# emonPlug_v1-1.net
KiCad netlist of a schematic drawn in EAGLE
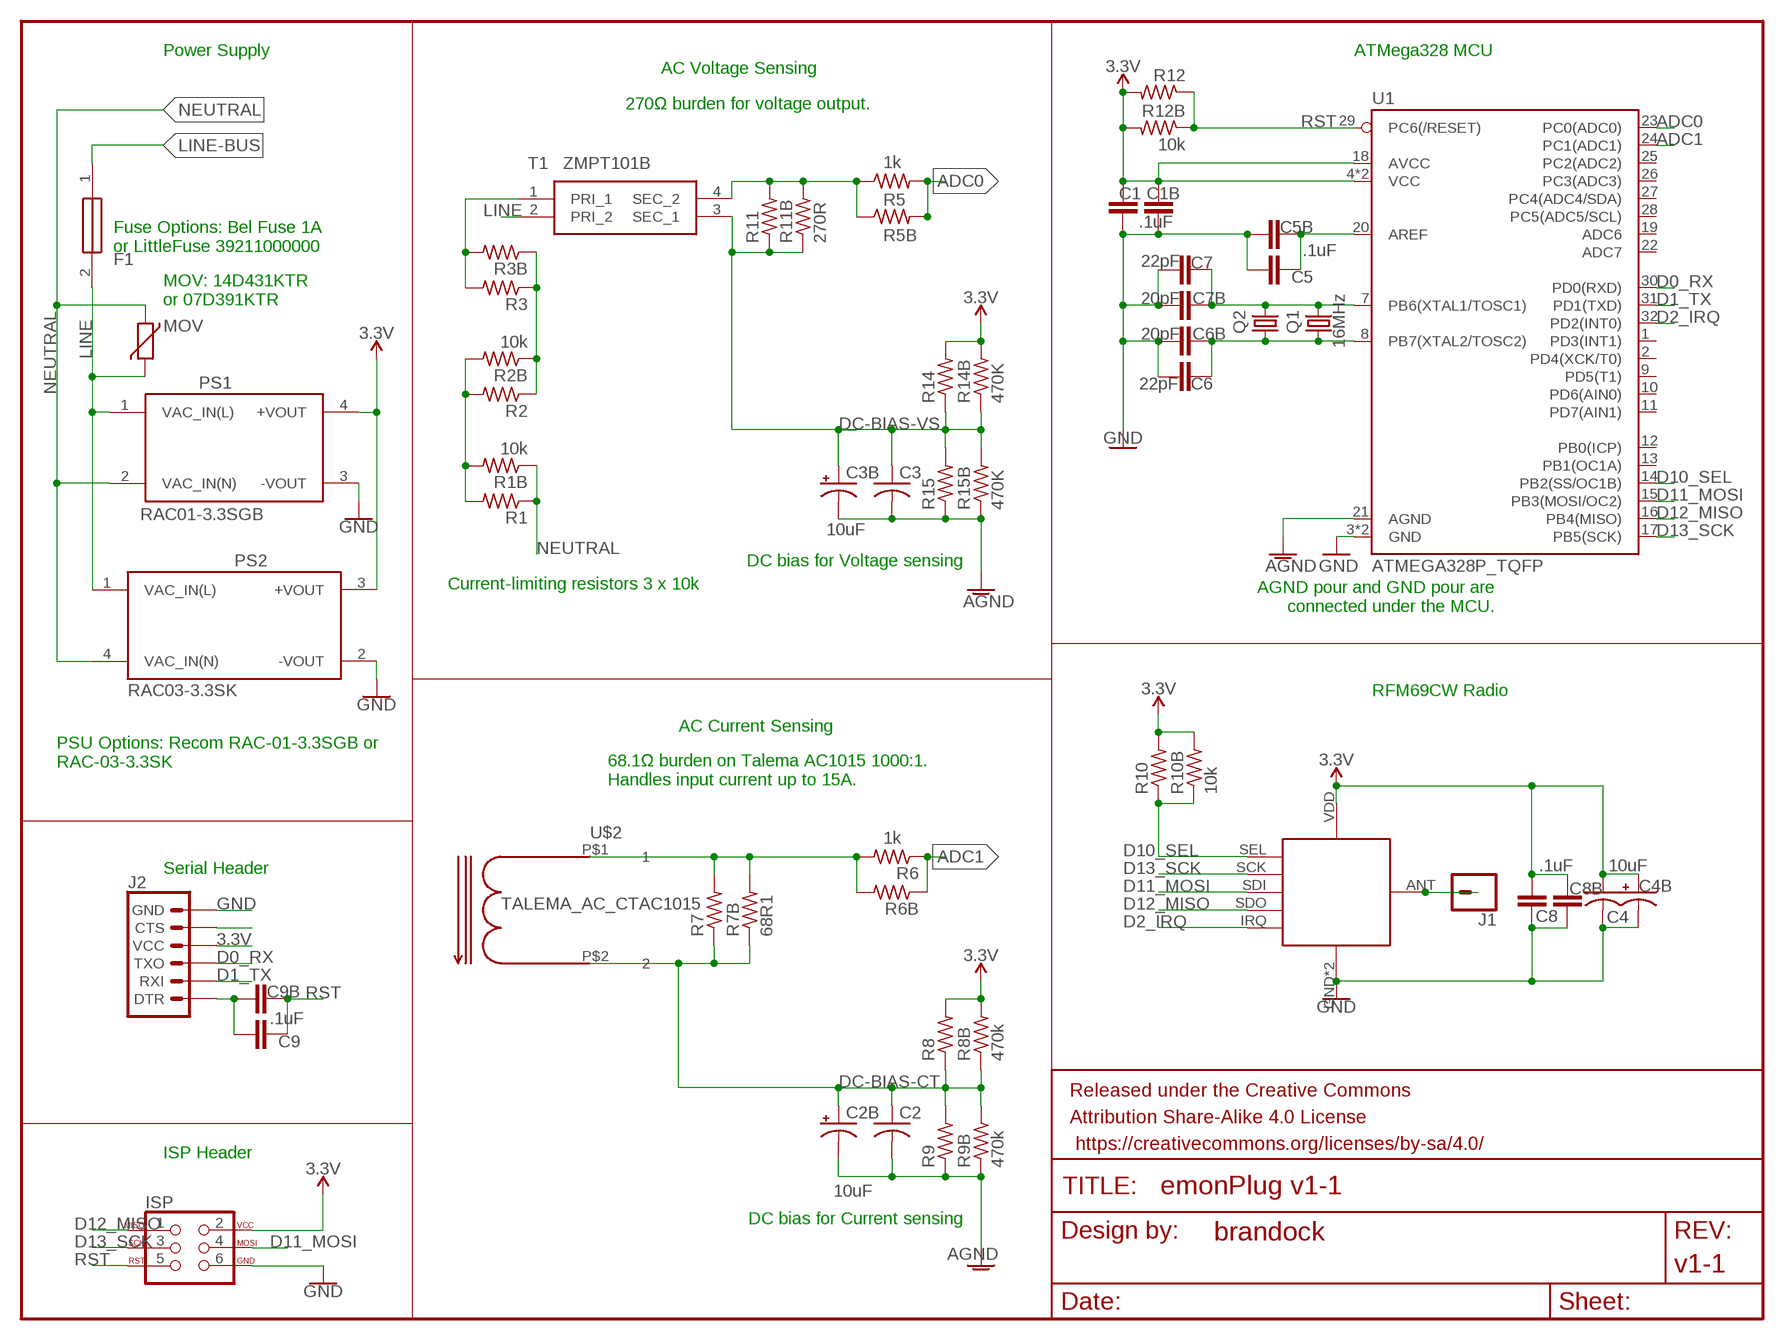
[diagram p0: schematic, sheet 1]

(export (version "E")
  (design (tool "Eeschema 10.0.6"))
  (components
    (comp (ref "C1")
      (value ".1uF")
      (footprint "eagle-import:C0805")
      (libsource (lib "eagle-import") (part "C-EUC0805"))
    )
    (comp (ref "C1B")
      (value ".1uF")
      (footprint "eagle-import:C025-024X044")
      (libsource (lib "eagle-import") (part "rcl_334_C-EU025-024X044"))
    )
    (comp (ref "C2")
      (value "C-USC0805")
      (footprint "eagle-import:C0805")
      (libsource (lib "eagle-import") (part "C-USC0805"))
    )
    (comp (ref "C2B")
      (value "10uF")
      (footprint "eagle-import:E1,8-4")
      (libsource (lib "eagle-import") (part "CPOL-USE1.8-4"))
    )
    (comp (ref "C3")
      (value "C-USC0805")
      (footprint "eagle-import:C0805")
      (libsource (lib "eagle-import") (part "C-USC0805"))
    )
    (comp (ref "C3B")
      (value "10uF")
      (footprint "eagle-import:E1,8-4")
      (libsource (lib "eagle-import") (part "CPOL-USE1.8-4"))
    )
    (comp (ref "C4")
      (value "10uF")
      (footprint "eagle-import:C0805")
      (libsource (lib "eagle-import") (part "C-USC0805"))
    )
    (comp (ref "C4B")
      (value "10uF")
      (footprint "eagle-import:E1,8-4")
      (libsource (lib "eagle-import") (part "CPOL-USE1.8-4"))
    )
    (comp (ref "C5")
      (value ".1uF")
      (footprint "eagle-import:C0805")
      (libsource (lib "eagle-import") (part "C-EUC0805"))
    )
    (comp (ref "C5B")
      (value ".1uF")
      (footprint "eagle-import:C025-024X044")
      (libsource (lib "eagle-import") (part "rcl_334_C-EU025-024X044"))
    )
    (comp (ref "C6")
      (value "22pF")
      (footprint "eagle-import:C0805")
      (libsource (lib "eagle-import") (part "C-EUC0805"))
    )
    (comp (ref "C6B")
      (value "20pF")
      (footprint "eagle-import:C025-024X044")
      (libsource (lib "eagle-import") (part "rcl_334_C-EU025-024X044"))
    )
    (comp (ref "C7")
      (value "22pF")
      (footprint "eagle-import:C0805")
      (libsource (lib "eagle-import") (part "C-EUC0805"))
    )
    (comp (ref "C7B")
      (value "20pF")
      (footprint "eagle-import:C025-024X044")
      (libsource (lib "eagle-import") (part "rcl_334_C-EU025-024X044"))
    )
    (comp (ref "C8")
      (value ".1uF")
      (footprint "eagle-import:C0805")
      (libsource (lib "eagle-import") (part "C-EUC0805"))
    )
    (comp (ref "C8B")
      (value ".1uF")
      (footprint "eagle-import:C025-024X044")
      (libsource (lib "eagle-import") (part "rcl_334_C-EU025-024X044"))
    )
    (comp (ref "C9")
      (value ".1uF")
      (footprint "eagle-import:C0805")
      (libsource (lib "eagle-import") (part "C-EUC0805"))
    )
    (comp (ref "C9B")
      (value ".1uF")
      (footprint "eagle-import:C025-024X044")
      (libsource (lib "eagle-import") (part "rcl_334_C-EU025-024X044"))
    )
    (comp (ref "F1")
      (value "39211000000")
      (footprint "eagle-import:39211000000")
      (fields (field (name "MOUSER_PART_NUMBER") "576-3921100000"))
      (libsource (lib "eagle-import") (part "39211000000"))
    )
    (comp (ref "FRAME1")
      (value "FRAME-LETTER")
      (footprint "eagle-import:CREATIVE_COMMONS")
      (fields (field (name "DESIGNER") "brandock") (field (name "REV") "v1-1"))
      (libsource (lib "eagle-import") (part "FRAME-LETTER"))
    )
    (comp (ref "ISP")
      (value "AVR_SPI_PROG_3X22X3_LOCK")
      (footprint "eagle-import:2X3_LOCK")
      (libsource (lib "eagle-import") (part "AVR_SPI_PROG_3X22X3_LOCK"))
    )
    (comp (ref "J1")
      (value "CONN_01")
      (footprint "eagle-import:1X01")
      (libsource (lib "eagle-import") (part "CONN_01"))
    )
    (comp (ref "J2")
      (value "6_PIN_SERIAL_TARGET_SILK")
      (footprint "eagle-import:1X06")
      (libsource (lib "eagle-import") (part "6_PIN_SERIAL_TARGET_SILK"))
    )
    (comp (ref "MOV")
      (value "VARISTOR-5")
      (footprint "eagle-import:R-5")
      (libsource (lib "eagle-import") (part "VARISTOR-5"))
    )
    (comp (ref "PS1")
      (value "RAC01-3.3SGB")
      (footprint "eagle-import:CONV_RAC01-3.3SGB")
      (fields (field (name "MF") "Recom Power"))
      (libsource (lib "eagle-import") (part "RAC01-3.3SGB"))
    )
    (comp (ref "PS2")
      (value "RAC03-3.3SK")
      (footprint "eagle-import:CONV_RAC03-3.3SK")
      (fields (field (name "MF") "Recom Power"))
      (libsource (lib "eagle-import") (part "RAC03-3.3SK"))
    )
    (comp (ref "Q1")
      (value "16MHz")
      (footprint "eagle-import:HC49_S-NO-SILK")
      (libsource (lib "eagle-import") (part "CRYSTALHC49S-NOSILK"))
    )
    (comp (ref "Q2")
      (value "CRYSTALHC49UP")
      (footprint "eagle-import:HC49UP")
      (libsource (lib "eagle-import") (part "crystal_204_CRYSTALHC49UP"))
    )
    (comp (ref "R1")
      (value "R-US_R0805")
      (footprint "eagle-import:R0805")
      (libsource (lib "eagle-import") (part "rcl_334_R-US_R0805"))
    )
    (comp (ref "R1B")
      (value "10k")
      (footprint "eagle-import:0204_7")
      (libsource (lib "eagle-import") (part "R-US_0204/7"))
    )
    (comp (ref "R2")
      (value "R-US_R0805")
      (footprint "eagle-import:R0805")
      (libsource (lib "eagle-import") (part "rcl_334_R-US_R0805"))
    )
    (comp (ref "R2B")
      (value "10k")
      (footprint "eagle-import:0204_7")
      (libsource (lib "eagle-import") (part "R-US_0204/7"))
    )
    (comp (ref "R3")
      (value "R-US_R0805")
      (footprint "eagle-import:R0805")
      (libsource (lib "eagle-import") (part "rcl_334_R-US_R0805"))
    )
    (comp (ref "R3B")
      (value "R-US_0204/7")
      (footprint "eagle-import:0204_7")
      (libsource (lib "eagle-import") (part "R-US_0204/7"))
    )
    (comp (ref "R5")
      (value "1k")
      (footprint "eagle-import:R0805")
      (libsource (lib "eagle-import") (part "rcl_334_R-US_R0805"))
    )
    (comp (ref "R5B")
      (value "R-US_0204/7")
      (footprint "eagle-import:0204_7")
      (libsource (lib "eagle-import") (part "R-US_0204/7"))
    )
    (comp (ref "R6")
      (value "R-US_R0805")
      (footprint "eagle-import:R0805")
      (libsource (lib "eagle-import") (part "rcl_334_R-US_R0805"))
    )
    (comp (ref "R6B")
      (value "1k")
      (footprint "eagle-import:0204_7")
      (libsource (lib "eagle-import") (part "R-US_0204/7"))
    )
    (comp (ref "R7")
      (value "R-US_R0805")
      (footprint "eagle-import:R0805")
      (libsource (lib "eagle-import") (part "rcl_334_R-US_R0805"))
    )
    (comp (ref "R7B")
      (value "68R1")
      (footprint "eagle-import:0204_7")
      (libsource (lib "eagle-import") (part "R-US_0204/7"))
    )
    (comp (ref "R8")
      (value "R-US_R0805")
      (footprint "eagle-import:R0805")
      (libsource (lib "eagle-import") (part "rcl_334_R-US_R0805"))
    )
    (comp (ref "R8B")
      (value "470k")
      (footprint "eagle-import:0204_7")
      (libsource (lib "eagle-import") (part "R-US_0204/7"))
    )
    (comp (ref "R9")
      (value "R-US_R0805")
      (footprint "eagle-import:R0805")
      (libsource (lib "eagle-import") (part "rcl_334_R-US_R0805"))
    )
    (comp (ref "R9B")
      (value "470k")
      (footprint "eagle-import:0204_7")
      (libsource (lib "eagle-import") (part "R-US_0204/7"))
    )
    (comp (ref "R10")
      (value "R-US_R0805")
      (footprint "eagle-import:R0805")
      (libsource (lib "eagle-import") (part "rcl_334_R-US_R0805"))
    )
    (comp (ref "R10B")
      (value "10k")
      (footprint "eagle-import:0204_7")
      (libsource (lib "eagle-import") (part "R-US_0204/7"))
    )
    (comp (ref "R11")
      (value "R-US_R0805")
      (footprint "eagle-import:R0805")
      (libsource (lib "eagle-import") (part "rcl_334_R-US_R0805"))
    )
    (comp (ref "R11B")
      (value "270R")
      (footprint "eagle-import:0204_7")
      (libsource (lib "eagle-import") (part "R-US_0204/7"))
    )
    (comp (ref "R12")
      (value "R-US_R0805")
      (footprint "eagle-import:R0805")
      (libsource (lib "eagle-import") (part "rcl_334_R-US_R0805"))
    )
    (comp (ref "R12B")
      (value "10k")
      (footprint "eagle-import:0204_7")
      (libsource (lib "eagle-import") (part "R-US_0204/7"))
    )
    (comp (ref "R14")
      (value "R-US_R0805")
      (footprint "eagle-import:R0805")
      (libsource (lib "eagle-import") (part "rcl_334_R-US_R0805"))
    )
    (comp (ref "R14B")
      (value "470K")
      (footprint "eagle-import:0204_7")
      (libsource (lib "eagle-import") (part "R-US_0204/7"))
    )
    (comp (ref "R15")
      (value "R-US_R0805")
      (footprint "eagle-import:R0805")
      (libsource (lib "eagle-import") (part "rcl_334_R-US_R0805"))
    )
    (comp (ref "R15B")
      (value "470K")
      (footprint "eagle-import:0204_7")
      (libsource (lib "eagle-import") (part "R-US_0204/7"))
    )
    (comp (ref "T1")
      (value "ZMPT101B")
      (footprint "eagle-import:ZMPT101B")
      (libsource (lib "eagle-import") (part "ZMPT101B"))
    )
    (comp (ref "U$2")
      (value "TALEMA_AC_CTAC1015")
      (footprint "eagle-import:AC1005-1020")
      (libsource (lib "eagle-import") (part "TALEMA_AC_CTAC1015"))
    )
    (comp (ref "U$3")
      (value "RFM12B_MINPADS")
      (footprint "eagle-import:RFM12B-MINPADS")
      (libsource (lib "eagle-import") (part "RFM12B_MINPADS"))
    )
    (comp (ref "U1")
      (value "ATMEGA328P_TQFP")
      (footprint "eagle-import:TQFP32-08")
      (libsource (lib "eagle-import") (part "ATMEGA328P_TQFP"))
    )
  )
  (nets
    (net (code "1") (name "3.3V") (class "Default")
      (node (ref "C1") (pin "2") (pinfunction "2_2") (pintype "passive"))
      (node (ref "C1B") (pin "1") (pinfunction "1_1") (pintype "passive"))
      (node (ref "C4") (pin "1") (pinfunction "1_1") (pintype "passive"))
      (node (ref "C4B") (pin "+") (pinfunction "+_+") (pintype "passive"))
      (node (ref "C8") (pin "1") (pinfunction "1_1") (pintype "passive"))
      (node (ref "C8B") (pin "1") (pinfunction "1_1") (pintype "passive"))
      (node (ref "ISP") (pin "2") (pinfunction "2_2") (pintype "passive"))
      (node (ref "J2") (pin "4") (pinfunction "VCC_4") (pintype "passive"))
      (node (ref "PS1") (pin "4") (pinfunction "+VOUT_4") (pintype "output"))
      (node (ref "PS2") (pin "3") (pinfunction "+VOUT_3") (pintype "output"))
      (node (ref "R10") (pin "2") (pinfunction "2_2") (pintype "passive"))
      (node (ref "R10B") (pin "2") (pinfunction "2_2") (pintype "passive"))
      (node (ref "R12") (pin "2") (pinfunction "2_2") (pintype "passive"))
      (node (ref "R12B") (pin "2") (pinfunction "2_2") (pintype "passive"))
      (node (ref "R14") (pin "2") (pinfunction "2_2") (pintype "passive"))
      (node (ref "R14B") (pin "2") (pinfunction "2_2") (pintype "passive"))
      (node (ref "R8") (pin "2") (pinfunction "2_2") (pintype "passive"))
      (node (ref "R8B") (pin "2") (pinfunction "2_2") (pintype "passive"))
      (node (ref "U$3") (pin "VDD") (pinfunction "VDD_VDD") (pintype "bidirectional"))
      (node (ref "U1") (pin "18") (pinfunction "AVCC_18") (pintype "bidirectional"))
      (node (ref "U1") (pin "4") (pinfunction "VCC_4") (pintype "bidirectional"))
      (node (ref "U1") (pin "6") (pinfunction "VCC_6") (pintype "bidirectional"))
    )
    (net (code "2") (name "ADC0") (class "Default")
      (node (ref "R5") (pin "2") (pinfunction "2_2") (pintype "passive"))
      (node (ref "R5B") (pin "2") (pinfunction "2_2") (pintype "passive"))
      (node (ref "U1") (pin "23") (pinfunction "PC0(ADC0)_23") (pintype "bidirectional"))
    )
    (net (code "3") (name "ADC1") (class "Default")
      (node (ref "R6") (pin "1") (pinfunction "1_1") (pintype "passive"))
      (node (ref "R6B") (pin "1") (pinfunction "1_1") (pintype "passive"))
      (node (ref "U1") (pin "24") (pinfunction "PC1(ADC1)_24") (pintype "bidirectional"))
    )
    (net (code "4") (name "AGND") (class "Default")
      (node (ref "C2") (pin "2") (pinfunction "2_2") (pintype "passive"))
      (node (ref "C2B") (pin "-") (pinfunction "-_-") (pintype "passive"))
      (node (ref "C3") (pin "2") (pinfunction "2_2") (pintype "passive"))
      (node (ref "C3B") (pin "-") (pinfunction "-_-") (pintype "passive"))
      (node (ref "R15") (pin "1") (pinfunction "1_1") (pintype "passive"))
      (node (ref "R15B") (pin "1") (pinfunction "1_1") (pintype "passive"))
      (node (ref "R9") (pin "1") (pinfunction "1_1") (pintype "passive"))
      (node (ref "R9B") (pin "1") (pinfunction "1_1") (pintype "passive"))
      (node (ref "U1") (pin "21") (pinfunction "AGND_21") (pintype "bidirectional"))
    )
    (net (code "5") (name "D0_RX") (class "Default")
      (node (ref "J2") (pin "3") (pinfunction "TXO_3") (pintype "passive"))
      (node (ref "U1") (pin "30") (pinfunction "PD0(RXD)_30") (pintype "bidirectional"))
    )
    (net (code "6") (name "D1_TX") (class "Default")
      (node (ref "J2") (pin "2") (pinfunction "RXI_2") (pintype "passive"))
      (node (ref "U1") (pin "31") (pinfunction "PD1(TXD)_31") (pintype "bidirectional"))
    )
    (net (code "7") (name "D2_IRQ") (class "Default")
      (node (ref "U$3") (pin "IRQ") (pinfunction "IRQ_IRQ") (pintype "bidirectional"))
      (node (ref "U1") (pin "32") (pinfunction "PD2(INT0)_32") (pintype "bidirectional"))
    )
    (net (code "8") (name "D10_SEL") (class "Default")
      (node (ref "R10") (pin "1") (pinfunction "1_1") (pintype "passive"))
      (node (ref "R10B") (pin "1") (pinfunction "1_1") (pintype "passive"))
      (node (ref "U$3") (pin "SEL") (pinfunction "SEL_SEL") (pintype "bidirectional"))
      (node (ref "U1") (pin "14") (pinfunction "PB2(SS/OC1B)_14") (pintype "bidirectional"))
    )
    (net (code "9") (name "D11_MOSI") (class "Default")
      (node (ref "ISP") (pin "4") (pinfunction "4_4") (pintype "passive"))
      (node (ref "U$3") (pin "SDI") (pinfunction "SDI/MOSI_SDI") (pintype "bidirectional"))
      (node (ref "U1") (pin "15") (pinfunction "PB3(MOSI/OC2)_15") (pintype "bidirectional"))
    )
    (net (code "10") (name "D12_MISO") (class "Default")
      (node (ref "ISP") (pin "1") (pinfunction "1_1") (pintype "passive"))
      (node (ref "U$3") (pin "SDO") (pinfunction "SDO/MISO_SDO") (pintype "bidirectional"))
      (node (ref "U1") (pin "16") (pinfunction "PB4(MISO)_16") (pintype "bidirectional"))
    )
    (net (code "11") (name "D13_SCK") (class "Default")
      (node (ref "ISP") (pin "3") (pinfunction "3_3") (pintype "passive"))
      (node (ref "U$3") (pin "SCK") (pinfunction "SCK_SCK") (pintype "bidirectional"))
      (node (ref "U1") (pin "17") (pinfunction "PB5(SCK)_17") (pintype "bidirectional"))
    )
    (net (code "12") (name "DC-BIAS-CT") (class "Default")
      (node (ref "C2") (pin "1") (pinfunction "1_1") (pintype "passive"))
      (node (ref "C2B") (pin "+") (pinfunction "+_+") (pintype "passive"))
      (node (ref "R7") (pin "1") (pinfunction "1_1") (pintype "passive"))
      (node (ref "R7B") (pin "1") (pinfunction "1_1") (pintype "passive"))
      (node (ref "R8") (pin "1") (pinfunction "1_1") (pintype "passive"))
      (node (ref "R8B") (pin "1") (pinfunction "1_1") (pintype "passive"))
      (node (ref "R9") (pin "2") (pinfunction "2_2") (pintype "passive"))
      (node (ref "R9B") (pin "2") (pinfunction "2_2") (pintype "passive"))
      (node (ref "U$2") (pin "P$2") (pinfunction "2_P$2") (pintype "bidirectional"))
    )
    (net (code "13") (name "DC-BIAS-VS") (class "Default")
      (node (ref "C3") (pin "1") (pinfunction "1_1") (pintype "passive"))
      (node (ref "C3B") (pin "+") (pinfunction "+_+") (pintype "passive"))
      (node (ref "R11") (pin "1") (pinfunction "1_1") (pintype "passive"))
      (node (ref "R11B") (pin "1") (pinfunction "1_1") (pintype "passive"))
      (node (ref "R14") (pin "1") (pinfunction "1_1") (pintype "passive"))
      (node (ref "R14B") (pin "1") (pinfunction "1_1") (pintype "passive"))
      (node (ref "R15") (pin "2") (pinfunction "2_2") (pintype "passive"))
      (node (ref "R15B") (pin "2") (pinfunction "2_2") (pintype "passive"))
      (node (ref "T1") (pin "3") (pinfunction "SEC_1_3") (pintype "bidirectional"))
    )
    (net (code "14") (name "GND") (class "Default")
      (node (ref "C1") (pin "1") (pinfunction "1_1") (pintype "passive"))
      (node (ref "C1B") (pin "2") (pinfunction "2_2") (pintype "passive"))
      (node (ref "C4") (pin "2") (pinfunction "2_2") (pintype "passive"))
      (node (ref "C4B") (pin "-") (pinfunction "-_-") (pintype "passive"))
      (node (ref "C5") (pin "1") (pinfunction "1_1") (pintype "passive"))
      (node (ref "C5B") (pin "1") (pinfunction "1_1") (pintype "passive"))
      (node (ref "C6") (pin "2") (pinfunction "2_2") (pintype "passive"))
      (node (ref "C6B") (pin "2") (pinfunction "2_2") (pintype "passive"))
      (node (ref "C7") (pin "2") (pinfunction "2_2") (pintype "passive"))
      (node (ref "C7B") (pin "2") (pinfunction "2_2") (pintype "passive"))
      (node (ref "C8") (pin "2") (pinfunction "2_2") (pintype "passive"))
      (node (ref "C8B") (pin "2") (pinfunction "2_2") (pintype "passive"))
      (node (ref "ISP") (pin "6") (pinfunction "6_6") (pintype "passive"))
      (node (ref "J2") (pin "6") (pinfunction "GND_6") (pintype "passive"))
      (node (ref "PS1") (pin "3") (pinfunction "-VOUT_3") (pintype "output"))
      (node (ref "PS2") (pin "2") (pinfunction "-VOUT_2") (pintype "output"))
      (node (ref "U$3") (pin "GND") (pinfunction "GND_GND") (pintype "bidirectional"))
      (node (ref "U$3") (pin "GND2") (pinfunction "GND_GND2") (pintype "bidirectional"))
      (node (ref "U1") (pin "3") (pinfunction "GND_3") (pintype "bidirectional"))
      (node (ref "U1") (pin "5") (pinfunction "GND_5") (pintype "bidirectional"))
    )
    (net (code "15") (name "LINE") (class "Default")
      (node (ref "F1") (pin "2") (pinfunction "2_2") (pintype "bidirectional"))
      (node (ref "MOV") (pin "1") (pinfunction "1_1") (pintype "passive"))
      (node (ref "PS1") (pin "1") (pinfunction "VAC_IN(L)_1") (pintype "input"))
      (node (ref "PS2") (pin "1") (pinfunction "VAC_IN(L)_1") (pintype "input"))
      (node (ref "T1") (pin "2") (pinfunction "PRI_2_2") (pintype "bidirectional"))
    )
    (net (code "16") (name "LINE-BUS") (class "Default")
      (node (ref "F1") (pin "1") (pinfunction "1_1") (pintype "bidirectional"))
    )
    (net (code "17") (name "NEUTRAL") (class "Default")
      (node (ref "MOV") (pin "2") (pinfunction "2_2") (pintype "passive"))
      (node (ref "PS1") (pin "2") (pinfunction "VAC_IN(N)_2") (pintype "input"))
      (node (ref "PS2") (pin "4") (pinfunction "VAC_IN(N)_4") (pintype "input"))
      (node (ref "R1") (pin "1") (pinfunction "1_1") (pintype "passive"))
      (node (ref "R1B") (pin "1") (pinfunction "1_1") (pintype "passive"))
    )
    (net (code "18") (name "Net-(J1-Pad1)") (class "Default")
      (node (ref "J1") (pin "1") (pinfunction "1_1") (pintype "passive"))
      (node (ref "U$3") (pin "ANT") (pinfunction "ANT_ANT") (pintype "bidirectional"))
    )
    (net (code "19") (name "Net-(J2-DTR)") (class "Default")
      (node (ref "C9") (pin "1") (pinfunction "1_1") (pintype "passive"))
      (node (ref "C9B") (pin "1") (pinfunction "1_1") (pintype "passive"))
      (node (ref "J2") (pin "1") (pinfunction "DTR_1") (pintype "passive"))
    )
    (net (code "20") (name "Net-(R1-Pad2)") (class "Default")
      (node (ref "R1") (pin "2") (pinfunction "2_2") (pintype "passive"))
      (node (ref "R1B") (pin "2") (pinfunction "2_2") (pintype "passive"))
      (node (ref "R2") (pin "2") (pinfunction "2_2") (pintype "passive"))
      (node (ref "R2B") (pin "2") (pinfunction "2_2") (pintype "passive"))
    )
    (net (code "21") (name "Net-(R2-Pad1)") (class "Default")
      (node (ref "R2") (pin "1") (pinfunction "1_1") (pintype "passive"))
      (node (ref "R2B") (pin "1") (pinfunction "1_1") (pintype "passive"))
      (node (ref "R3") (pin "1") (pinfunction "1_1") (pintype "passive"))
      (node (ref "R3B") (pin "1") (pinfunction "1_1") (pintype "passive"))
    )
    (net (code "22") (name "Net-(T1-PRI_1)") (class "Default")
      (node (ref "R3") (pin "2") (pinfunction "2_2") (pintype "passive"))
      (node (ref "R3B") (pin "2") (pinfunction "2_2") (pintype "passive"))
      (node (ref "T1") (pin "1") (pinfunction "PRI_1_1") (pintype "bidirectional"))
    )
    (net (code "23") (name "Net-(T1-SEC_2)") (class "Default")
      (node (ref "R11") (pin "2") (pinfunction "2_2") (pintype "passive"))
      (node (ref "R11B") (pin "2") (pinfunction "2_2") (pintype "passive"))
      (node (ref "R5") (pin "1") (pinfunction "1_1") (pintype "passive"))
      (node (ref "R5B") (pin "1") (pinfunction "1_1") (pintype "passive"))
      (node (ref "T1") (pin "4") (pinfunction "SEC_2_4") (pintype "bidirectional"))
    )
    (net (code "24") (name "Net-(U$2-1)") (class "Default")
      (node (ref "R6") (pin "2") (pinfunction "2_2") (pintype "passive"))
      (node (ref "R6B") (pin "2") (pinfunction "2_2") (pintype "passive"))
      (node (ref "R7") (pin "2") (pinfunction "2_2") (pintype "passive"))
      (node (ref "R7B") (pin "2") (pinfunction "2_2") (pintype "passive"))
      (node (ref "U$2") (pin "P$1") (pinfunction "1_P$1") (pintype "bidirectional"))
    )
    (net (code "25") (name "Net-(U1-AREF)") (class "Default")
      (node (ref "C5") (pin "2") (pinfunction "2_2") (pintype "passive"))
      (node (ref "C5B") (pin "2") (pinfunction "2_2") (pintype "passive"))
      (node (ref "U1") (pin "20") (pinfunction "AREF_20") (pintype "bidirectional"))
    )
    (net (code "26") (name "Net-(U1-PB6(XTAL1{slash}TOSC1))") (class "Default")
      (node (ref "C7") (pin "1") (pinfunction "1_1") (pintype "passive"))
      (node (ref "C7B") (pin "1") (pinfunction "1_1") (pintype "passive"))
      (node (ref "Q1") (pin "2") (pinfunction "2_2") (pintype "passive"))
      (node (ref "Q2") (pin "2") (pinfunction "2_2") (pintype "passive"))
      (node (ref "U1") (pin "7") (pinfunction "PB6(XTAL1/TOSC1)_7") (pintype "bidirectional"))
    )
    (net (code "27") (name "Net-(U1-PB7(XTAL2{slash}TOSC2))") (class "Default")
      (node (ref "C6") (pin "1") (pinfunction "1_1") (pintype "passive"))
      (node (ref "C6B") (pin "1") (pinfunction "1_1") (pintype "passive"))
      (node (ref "Q1") (pin "1") (pinfunction "1_1") (pintype "passive"))
      (node (ref "Q2") (pin "1") (pinfunction "1_1") (pintype "passive"))
      (node (ref "U1") (pin "8") (pinfunction "PB7(XTAL2/TOSC2)_8") (pintype "bidirectional"))
    )
    (net (code "28") (name "RST") (class "Default")
      (node (ref "C9") (pin "2") (pinfunction "2_2") (pintype "passive"))
      (node (ref "C9B") (pin "2") (pinfunction "2_2") (pintype "passive"))
      (node (ref "ISP") (pin "5") (pinfunction "5_5") (pintype "passive"))
      (node (ref "R12") (pin "1") (pinfunction "1_1") (pintype "passive"))
      (node (ref "R12B") (pin "1") (pinfunction "1_1") (pintype "passive"))
      (node (ref "U1") (pin "29") (pinfunction "PC6(/RESET)_29") (pintype "bidirectional"))
    )
    (net (code "29") (name "unconnected-(J2-CTS-Pad5)") (class "Default")
      (node (ref "J2") (pin "5") (pinfunction "CTS_5") (pintype "passive"))
    )
    (net (code "30") (name "unconnected-(U1-ADC6-Pad19)") (class "Default")
      (node (ref "U1") (pin "19") (pinfunction "ADC6_19") (pintype "bidirectional"))
    )
    (net (code "31") (name "unconnected-(U1-ADC7-Pad22)") (class "Default")
      (node (ref "U1") (pin "22") (pinfunction "ADC7_22") (pintype "bidirectional"))
    )
    (net (code "32") (name "unconnected-(U1-PB0(ICP)-Pad12)") (class "Default")
      (node (ref "U1") (pin "12") (pinfunction "PB0(ICP)_12") (pintype "bidirectional"))
    )
    (net (code "33") (name "unconnected-(U1-PB1(OC1A)-Pad13)") (class "Default")
      (node (ref "U1") (pin "13") (pinfunction "PB1(OC1A)_13") (pintype "bidirectional"))
    )
    (net (code "34") (name "unconnected-(U1-PC2(ADC2)-Pad25)") (class "Default")
      (node (ref "U1") (pin "25") (pinfunction "PC2(ADC2)_25") (pintype "bidirectional"))
    )
    (net (code "35") (name "unconnected-(U1-PC3(ADC3)-Pad26)") (class "Default")
      (node (ref "U1") (pin "26") (pinfunction "PC3(ADC3)_26") (pintype "bidirectional"))
    )
    (net (code "36") (name "unconnected-(U1-PC4(ADC4{slash}SDA)-Pad27)") (class "Default")
      (node (ref "U1") (pin "27") (pinfunction "PC4(ADC4/SDA)_27") (pintype "bidirectional"))
    )
    (net (code "37") (name "unconnected-(U1-PC5(ADC5{slash}SCL)-Pad28)") (class "Default")
      (node (ref "U1") (pin "28") (pinfunction "PC5(ADC5/SCL)_28") (pintype "bidirectional"))
    )
    (net (code "38") (name "unconnected-(U1-PD3(INT1)-Pad1)") (class "Default")
      (node (ref "U1") (pin "1") (pinfunction "PD3(INT1)_1") (pintype "bidirectional"))
    )
    (net (code "39") (name "unconnected-(U1-PD4(XCK{slash}T0)-Pad2)") (class "Default")
      (node (ref "U1") (pin "2") (pinfunction "PD4(XCK/T0)_2") (pintype "bidirectional"))
    )
    (net (code "40") (name "unconnected-(U1-PD5(T1)-Pad9)") (class "Default")
      (node (ref "U1") (pin "9") (pinfunction "PD5(T1)_9") (pintype "bidirectional"))
    )
    (net (code "41") (name "unconnected-(U1-PD6(AIN0)-Pad10)") (class "Default")
      (node (ref "U1") (pin "10") (pinfunction "PD6(AIN0)_10") (pintype "bidirectional"))
    )
    (net (code "42") (name "unconnected-(U1-PD7(AIN1)-Pad11)") (class "Default")
      (node (ref "U1") (pin "11") (pinfunction "PD7(AIN1)_11") (pintype "bidirectional"))
    )
  )
)
